# Supply.net
KiCad netlist of a schematic drawn in Altium Designer
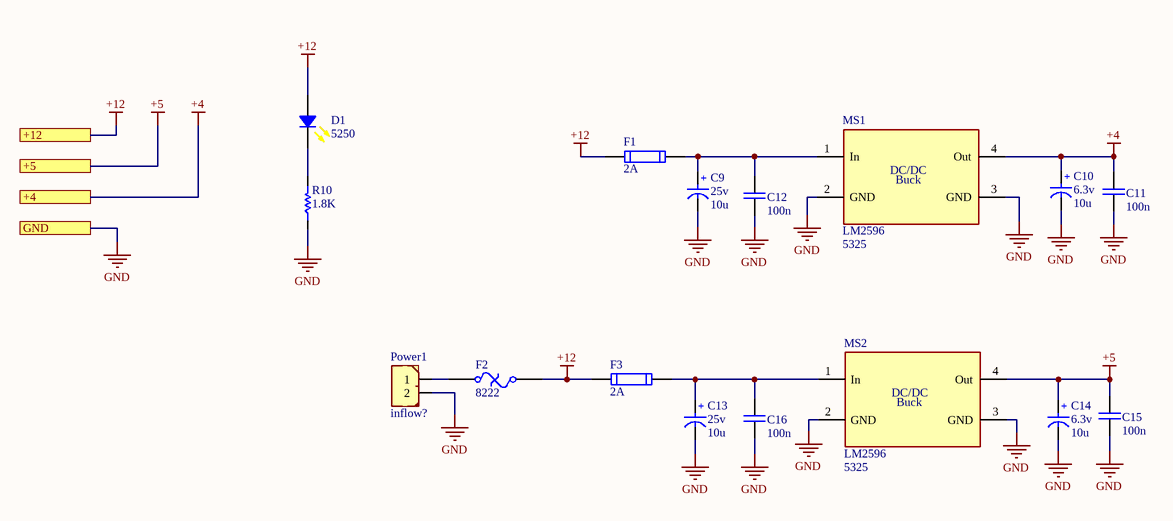
[diagram p0: Supply.SchDoc]

(export (version "E")
  (design (tool "Eeschema 10.0.6"))
  (components
    (comp (ref "C9")
      (value "10u")
      (footprint "SMT_C_Tantalum_B")
      (description "Tantalum Capacitor,TAJ Series-SMD")
      (fields (field (name "RATING") "25v") (field (name "VALIDATION") "Valid"))
      (libsource (lib "aKaReZa") (part "Cap_Tantalum"))
    )
    (comp (ref "C10")
      (value "10u")
      (footprint "SMT_C_Tantalum_B")
      (description "Tantalum Capacitor,TAJ Series-SMD")
      (fields (field (name "RATING") "6.3v") (field (name "VALIDATION") "Valid"))
      (libsource (lib "aKaReZa") (part "Cap_Tantalum"))
    )
    (comp (ref "C11")
      (value "100n")
      (footprint "CAP 1206/3216")
      (description "Bipolar ceramic capacitor SMD")
      (fields (field (name "VALIDATION") "Valid"))
      (libsource (lib "aKaReZa") (part "Cap_Multi_SMD_100nF_1206"))
    )
    (comp (ref "C12")
      (value "100n")
      (footprint "CAP 1206/3216")
      (description "Bipolar ceramic capacitor SMD")
      (fields (field (name "VALIDATION") "Valid"))
      (libsource (lib "aKaReZa") (part "Cap_Multi_SMD_100nF_1206"))
    )
    (comp (ref "C13")
      (value "10u")
      (footprint "SMT_C_Tantalum_B")
      (description "Tantalum Capacitor,TAJ Series-SMD")
      (fields (field (name "RATING") "25v") (field (name "VALIDATION") "Valid"))
      (libsource (lib "aKaReZa") (part "Cap_Tantalum"))
    )
    (comp (ref "C14")
      (value "10u")
      (footprint "SMT_C_Tantalum_B")
      (description "Tantalum Capacitor,TAJ Series-SMD")
      (fields (field (name "RATING") "6.3v") (field (name "VALIDATION") "Valid"))
      (libsource (lib "aKaReZa") (part "Cap_Tantalum"))
    )
    (comp (ref "C15")
      (value "100n")
      (footprint "CAP 1206/3216")
      (description "Bipolar ceramic capacitor SMD")
      (fields (field (name "VALIDATION") "Valid"))
      (libsource (lib "aKaReZa") (part "Cap_Multi_SMD_100nF_1206"))
    )
    (comp (ref "C16")
      (value "100n")
      (footprint "CAP 1206/3216")
      (description "Bipolar ceramic capacitor SMD")
      (fields (field (name "VALIDATION") "Valid"))
      (libsource (lib "aKaReZa") (part "Cap_Multi_SMD_100nF_1206"))
    )
    (comp (ref "D1")
      (value "Yellow, 1206")
      (footprint "LED 1206/3216 YELLOW")
      (description "LED")
      (fields (field (name "INFLOW") "5250") (field (name "VALIDATION") "Valid"))
      (libsource (lib "aKaReZa") (part "Semi_LED_Yellow_1206"))
    )
    (comp (ref "F1")
      (value "2A")
      (footprint "1206_F")
      (description "Short circiut  protection")
      (fields (field (name "VALIDATION") "Valid"))
      (libsource (lib "aKaReZa") (part "Other_Elec_Fuse_SMD"))
    )
    (comp (ref "F2")
      (value "180'C, 10'A")
      (footprint "PIN-W2/E2.8")
      (description "Thermal Fuse")
      (fields (field (name "INFLOW") "8222") (field (name "VALIDATION") "NT"))
      (libsource (lib "aKaReZa") (part "Other_Elec_Fuse_Thermal"))
    )
    (comp (ref "F3")
      (value "2A")
      (footprint "1206_F")
      (description "Short circiut  protection")
      (fields (field (name "VALIDATION") "Valid"))
      (libsource (lib "aKaReZa") (part "Other_Elec_Fuse_SMD"))
    )
    (comp (ref "MS1")
      (value "LM2596")
      (footprint "LM2596_modsen")
      (description "DC to DC Buck converter 1.23V-30V 3A")
      (fields (field (name "INFLOW") "5325") (field (name "VALIDATION") "Valid"))
      (libsource (lib "aKaReZa") (part "ModSen_LM2596"))
    )
    (comp (ref "MS2")
      (value "LM2596")
      (footprint "LM2596_modsen")
      (description "DC to DC Buck converter 1.23V-30V 3A")
      (fields (field (name "INFLOW") "5325") (field (name "VALIDATION") "Valid"))
      (libsource (lib "aKaReZa") (part "ModSen_LM2596"))
    )
    (comp (ref "Power1")
      (value "2'Pin")
      (footprint "Phoenix_2PIN_RA_P5.08mm")
      (description "Power Connector 2'Pin")
      (fields (field (name "INFLOW") "inflow?") (field (name "VALIDATION") "NT"))
      (libsource (lib "aKaReZa") (part "Con_Power_2"))
    )
    (comp (ref "R10")
      (value "1.8K")
      (footprint "RES 1206 (3216X08L)")
      (description "Resistor")
      (fields (field (name "VALIDATION") "Valid"))
      (libsource (lib "aKaReZa") (part "Res_SMD_1206"))
    )
  )
  (nets
    (net (code "1") (name "+4") (class "Default")
      (node (ref "C10") (pin "1") (pinfunction "+_1") (pintype "passive"))
      (node (ref "C11") (pin "1") (pinfunction "1_1") (pintype "passive"))
      (node (ref "MS1") (pin "4") (pinfunction "Out_4") (pintype "power_in"))
    )
    (net (code "2") (name "+5") (class "Default")
      (node (ref "C14") (pin "1") (pinfunction "+_1") (pintype "passive"))
      (node (ref "C15") (pin "1") (pinfunction "1_1") (pintype "passive"))
      (node (ref "MS2") (pin "4") (pinfunction "Out_4") (pintype "power_in"))
    )
    (net (code "3") (name "+12") (class "Default")
      (node (ref "D1") (pin "1") (pinfunction "1_1") (pintype "passive"))
      (node (ref "F1") (pin "1") (pinfunction "1_1") (pintype "passive"))
      (node (ref "F2") (pin "2") (pinfunction "2_2") (pintype "passive"))
      (node (ref "F3") (pin "1") (pinfunction "1_1") (pintype "passive"))
    )
    (net (code "4") (name "GND") (class "Default")
      (node (ref "C10") (pin "2") (pinfunction "-_2") (pintype "passive"))
      (node (ref "C11") (pin "2") (pinfunction "2_2") (pintype "passive"))
      (node (ref "C12") (pin "2") (pinfunction "2_2") (pintype "passive"))
      (node (ref "C13") (pin "2") (pinfunction "-_2") (pintype "passive"))
      (node (ref "C14") (pin "2") (pinfunction "-_2") (pintype "passive"))
      (node (ref "C15") (pin "2") (pinfunction "2_2") (pintype "passive"))
      (node (ref "C16") (pin "2") (pinfunction "2_2") (pintype "passive"))
      (node (ref "C9") (pin "2") (pinfunction "-_2") (pintype "passive"))
      (node (ref "MS1") (pin "2") (pinfunction "GND_2") (pintype "power_in"))
      (node (ref "MS1") (pin "3") (pinfunction "GND_3") (pintype "power_in"))
      (node (ref "MS2") (pin "2") (pinfunction "GND_2") (pintype "power_in"))
      (node (ref "MS2") (pin "3") (pinfunction "GND_3") (pintype "power_in"))
      (node (ref "Power1") (pin "2") (pinfunction "2_2") (pintype "passive"))
      (node (ref "R10") (pin "1") (pinfunction "1_1") (pintype "passive"))
    )
    (net (code "5") (name "Net-(C9-+)") (class "Default")
      (node (ref "C12") (pin "1") (pinfunction "1_1") (pintype "passive"))
      (node (ref "C9") (pin "1") (pinfunction "+_1") (pintype "passive"))
      (node (ref "F1") (pin "2") (pinfunction "2_2") (pintype "passive"))
      (node (ref "MS1") (pin "1") (pinfunction "In_1") (pintype "power_in"))
    )
    (net (code "6") (name "Net-(C13-+)") (class "Default")
      (node (ref "C13") (pin "1") (pinfunction "+_1") (pintype "passive"))
      (node (ref "C16") (pin "1") (pinfunction "1_1") (pintype "passive"))
      (node (ref "F3") (pin "2") (pinfunction "2_2") (pintype "passive"))
      (node (ref "MS2") (pin "1") (pinfunction "In_1") (pintype "power_in"))
    )
    (net (code "7") (name "Net-(D1-Pad2)") (class "Default")
      (node (ref "D1") (pin "2") (pinfunction "2_2") (pintype "passive"))
      (node (ref "R10") (pin "2") (pinfunction "2_2") (pintype "passive"))
    )
    (net (code "8") (name "Net-(F2-Pad1)") (class "Default")
      (node (ref "F2") (pin "1") (pinfunction "1_1") (pintype "passive"))
      (node (ref "Power1") (pin "1") (pinfunction "1_1") (pintype "passive"))
    )
  )
)
